# raspi.net
KiCad netlist of a schematic drawn in EAGLE
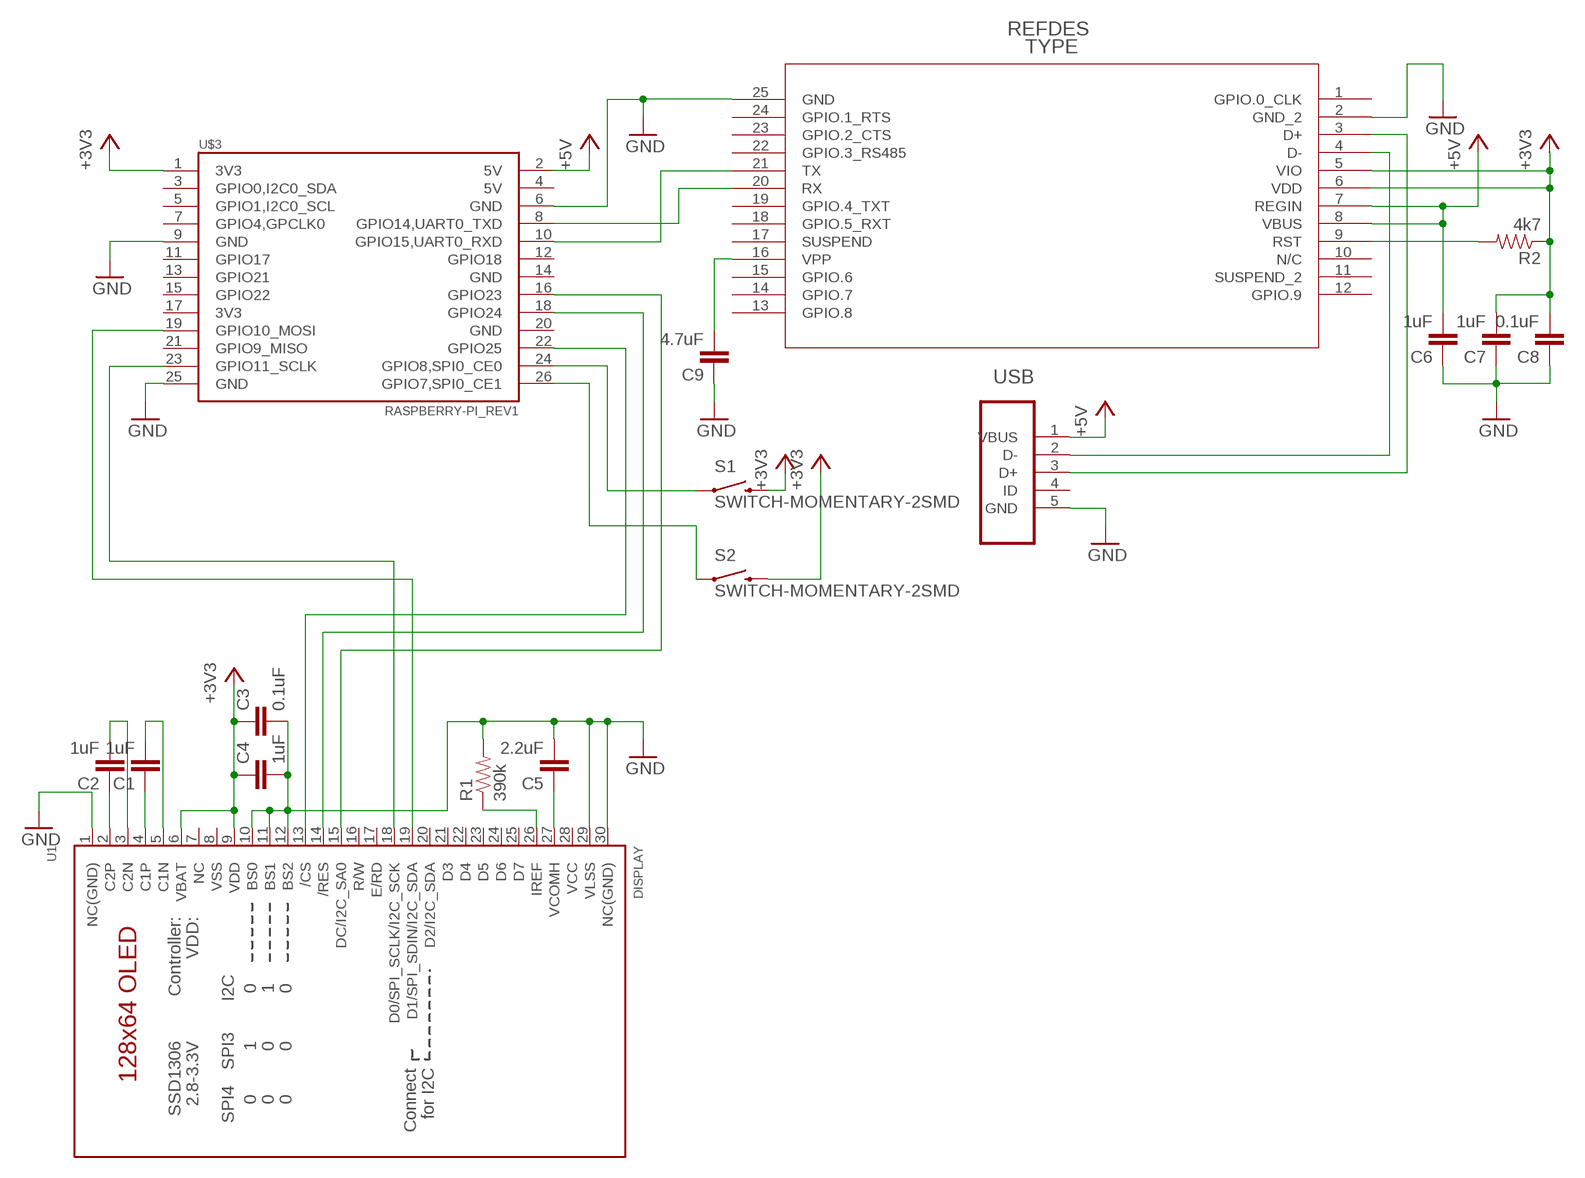
[diagram p0: schematic, sheet 1]

(export (version "E")
  (design (tool "Eeschema 10.0.6"))
  (components
    (comp (ref "C1")
      (value "1uF")
      (footprint "eagle-import:0805")
      (libsource (lib "eagle-import") (part "CAP0805"))
    )
    (comp (ref "C2")
      (value "1uF")
      (footprint "eagle-import:0805")
      (libsource (lib "eagle-import") (part "CAP0805"))
    )
    (comp (ref "C3")
      (value "0.1uF")
      (footprint "eagle-import:0805")
      (libsource (lib "eagle-import") (part "CAP0805"))
    )
    (comp (ref "C4")
      (value "1uF")
      (footprint "eagle-import:0805")
      (libsource (lib "eagle-import") (part "CAP0805"))
    )
    (comp (ref "C5")
      (value "2.2uF")
      (footprint "eagle-import:0805")
      (libsource (lib "eagle-import") (part "CAP0805"))
    )
    (comp (ref "C6")
      (value "1uF")
      (footprint "eagle-import:0805")
      (libsource (lib "eagle-import") (part "CAP0805"))
    )
    (comp (ref "C7")
      (value "1uF")
      (footprint "eagle-import:0805")
      (libsource (lib "eagle-import") (part "CAP0805"))
    )
    (comp (ref "C8")
      (value "0.1uF")
      (footprint "eagle-import:0805")
      (libsource (lib "eagle-import") (part "CAP0805"))
    )
    (comp (ref "C9")
      (value "4.7uF")
      (footprint "eagle-import:0805")
      (libsource (lib "eagle-import") (part "CAP0805"))
    )
    (comp (ref "R1")
      (value "390k")
      (footprint "eagle-import:0805")
      (libsource (lib "eagle-import") (part "RESISTOR0805-RES"))
    )
    (comp (ref "R2")
      (value "4k7")
      (footprint "eagle-import:0805")
      (libsource (lib "eagle-import") (part "RESISTOR0805-RES"))
    )
    (comp (ref "S1")
      (value "SWITCH-MOMENTARY-2SMD")
      (footprint "eagle-import:TACTILE_SWITCH_SMD")
      (libsource (lib "eagle-import") (part "SWITCH-MOMENTARY-2SMD"))
    )
    (comp (ref "S2")
      (value "SWITCH-MOMENTARY-2SMD")
      (footprint "eagle-import:TACTILE_SWITCH_SMD")
      (libsource (lib "eagle-import") (part "SWITCH-MOMENTARY-2SMD"))
    )
    (comp (ref "U$3")
      (value "RASPBERRY-PI_REV1")
      (footprint "eagle-import:RASPBERRY-PI_REV1")
      (libsource (lib "eagle-import") (part "RASPBERRY-PI_REV1"))
    )
    (comp (ref "U1")
      (value "DISPLAY")
      (footprint "eagle-import:UG-2864HSWEG01_0.96IN_WRAPAROUND")
      (libsource (lib "eagle-import") (part "DISP_OLED_UG-2864HSWEG010.96{dblquote}"))
    )
    (comp (ref "U2")
      (value "CP2110-F01-GM")
      (footprint "eagle-import:CP2110-F01-GM")
      (libsource (lib "eagle-import") (part "CP2110-F01-GM"))
    )
    (comp (ref "USB")
      (value "47346-0001")
      (footprint "eagle-import:MOLEX_47346-0001")
      (libsource (lib "eagle-import") (part "47346-0001"))
    )
  )
  (nets
    (net (code "1") (name "+3V3") (class "Default")
      (node (ref "C3") (pin "1") (pinfunction "1_1") (pintype "passive"))
      (node (ref "C4") (pin "1") (pinfunction "1_1") (pintype "passive"))
      (node (ref "C7") (pin "2") (pinfunction "2_2") (pintype "passive"))
      (node (ref "C8") (pin "2") (pinfunction "2_2") (pintype "passive"))
      (node (ref "R2") (pin "1") (pinfunction "1_1") (pintype "passive"))
      (node (ref "S1") (pin "3") (pinfunction "2_3") (pintype "passive"))
      (node (ref "S2") (pin "3") (pinfunction "2_3") (pintype "passive"))
      (node (ref "U$3") (pin "1") (pinfunction "3V3_1") (pintype "bidirectional"))
      (node (ref "U1") (pin "6") (pinfunction "VBAT_6") (pintype "input"))
      (node (ref "U1") (pin "9") (pinfunction "VDD_9") (pintype "power_in"))
      (node (ref "U2") (pin "5") (pinfunction "VIO_5") (pintype "passive"))
      (node (ref "U2") (pin "6") (pinfunction "VDD_6") (pintype "passive"))
    )
    (net (code "2") (name "+5V") (class "Default")
      (node (ref "C6") (pin "2") (pinfunction "2_2") (pintype "passive"))
      (node (ref "U$3") (pin "2") (pinfunction "5V_2") (pintype "bidirectional"))
      (node (ref "U2") (pin "7") (pinfunction "REGIN_7") (pintype "passive"))
      (node (ref "U2") (pin "8") (pinfunction "VBUS_8") (pintype "passive"))
      (node (ref "USB") (pin "1") (pinfunction "VBUS_1") (pintype "input"))
    )
    (net (code "3") (name "/VCC") (class "Default")
      (node (ref "U1") (pin "28") (pinfunction "VCC_28") (pintype "power_in"))
    )
    (net (code "4") (name "/VSS") (class "Default")
      (node (ref "U1") (pin "8") (pinfunction "VSS_8") (pintype "power_in"))
    )
    (net (code "5") (name "GND") (class "Default")
      (node (ref "C3") (pin "2") (pinfunction "2_2") (pintype "passive"))
      (node (ref "C4") (pin "2") (pinfunction "2_2") (pintype "passive"))
      (node (ref "C5") (pin "2") (pinfunction "2_2") (pintype "passive"))
      (node (ref "C6") (pin "1") (pinfunction "1_1") (pintype "passive"))
      (node (ref "C7") (pin "1") (pinfunction "1_1") (pintype "passive"))
      (node (ref "C8") (pin "1") (pinfunction "1_1") (pintype "passive"))
      (node (ref "C9") (pin "1") (pinfunction "1_1") (pintype "passive"))
      (node (ref "R1") (pin "2") (pinfunction "2_2") (pintype "passive"))
      (node (ref "U$3") (pin "25") (pinfunction "GND_25") (pintype "bidirectional"))
      (node (ref "U$3") (pin "6") (pinfunction "GND_6") (pintype "bidirectional"))
      (node (ref "U$3") (pin "9") (pinfunction "GND_9") (pintype "bidirectional"))
      (node (ref "U1") (pin "1") (pinfunction "NC(GND)_1") (pintype "input"))
      (node (ref "U1") (pin "10") (pinfunction "BS0_10") (pintype "input"))
      (node (ref "U1") (pin "11") (pinfunction "BS1_11") (pintype "input"))
      (node (ref "U1") (pin "12") (pinfunction "BS2_12") (pintype "input"))
      (node (ref "U1") (pin "29") (pinfunction "VLSS_29") (pintype "power_in"))
      (node (ref "U1") (pin "30") (pinfunction "NC(GND)_30") (pintype "input"))
      (node (ref "U2") (pin "2") (pinfunction "GND_2_2") (pintype "passive"))
      (node (ref "U2") (pin "25") (pinfunction "GND_25") (pintype "passive"))
      (node (ref "USB") (pin "5") (pinfunction "GND_5") (pintype "input"))
    )
    (net (code "6") (name "Net-(U$3-GPIO7,SPI0_CE1)") (class "Default")
      (node (ref "S2") (pin "1") (pinfunction "1_1") (pintype "passive"))
      (node (ref "U$3") (pin "26") (pinfunction "GPIO7,SPI0_CE1_26") (pintype "bidirectional"))
    )
    (net (code "7") (name "Net-(U$3-GPIO8,SPI0_CE0)") (class "Default")
      (node (ref "S1") (pin "1") (pinfunction "1_1") (pintype "passive"))
      (node (ref "U$3") (pin "24") (pinfunction "GPIO8,SPI0_CE0_24") (pintype "bidirectional"))
    )
    (net (code "8") (name "Net-(U$3-GPIO10_MOSI)") (class "Default")
      (node (ref "U$3") (pin "19") (pinfunction "GPIO10_MOSI_19") (pintype "bidirectional"))
      (node (ref "U1") (pin "19") (pinfunction "D1/SPI_SDIN/I2C_SDA_19") (pintype "bidirectional"))
    )
    (net (code "9") (name "Net-(U$3-GPIO11_SCLK)") (class "Default")
      (node (ref "U$3") (pin "23") (pinfunction "GPIO11_SCLK_23") (pintype "bidirectional"))
      (node (ref "U1") (pin "18") (pinfunction "D0/SPI_SCLK/I2C_SCK_18") (pintype "bidirectional"))
    )
    (net (code "10") (name "Net-(U$3-GPIO14,UART0_TXD)") (class "Default")
      (node (ref "U$3") (pin "8") (pinfunction "GPIO14,UART0_TXD_8") (pintype "bidirectional"))
      (node (ref "U2") (pin "20") (pinfunction "RX_20") (pintype "passive"))
    )
    (net (code "11") (name "Net-(U$3-GPIO15,UART0_RXD)") (class "Default")
      (node (ref "U$3") (pin "10") (pinfunction "GPIO15,UART0_RXD_10") (pintype "bidirectional"))
      (node (ref "U2") (pin "21") (pinfunction "TX_21") (pintype "passive"))
    )
    (net (code "12") (name "Net-(U$3-GPIO23)") (class "Default")
      (node (ref "U$3") (pin "16") (pinfunction "GPIO23_16") (pintype "bidirectional"))
      (node (ref "U1") (pin "15") (pinfunction "DC/I2C_SA0_15") (pintype "input"))
    )
    (net (code "13") (name "Net-(U$3-GPIO24)") (class "Default")
      (node (ref "U$3") (pin "18") (pinfunction "GPIO24_18") (pintype "bidirectional"))
      (node (ref "U1") (pin "14") (pinfunction "/RES_14") (pintype "input"))
    )
    (net (code "14") (name "Net-(U$3-GPIO25)") (class "Default")
      (node (ref "U$3") (pin "22") (pinfunction "GPIO25_22") (pintype "bidirectional"))
      (node (ref "U1") (pin "13") (pinfunction "/CS_13") (pintype "input"))
    )
    (net (code "15") (name "Net-(U1-C1N)") (class "Default")
      (node (ref "C1") (pin "2") (pinfunction "2_2") (pintype "passive"))
      (node (ref "U1") (pin "5") (pinfunction "C1N_5") (pintype "input"))
    )
    (net (code "16") (name "Net-(U1-C1P)") (class "Default")
      (node (ref "C1") (pin "1") (pinfunction "1_1") (pintype "passive"))
      (node (ref "U1") (pin "4") (pinfunction "C1P_4") (pintype "input"))
    )
    (net (code "17") (name "Net-(U1-C2N)") (class "Default")
      (node (ref "C2") (pin "2") (pinfunction "2_2") (pintype "passive"))
      (node (ref "U1") (pin "3") (pinfunction "C2N_3") (pintype "input"))
    )
    (net (code "18") (name "Net-(U1-C2P)") (class "Default")
      (node (ref "C2") (pin "1") (pinfunction "1_1") (pintype "passive"))
      (node (ref "U1") (pin "2") (pinfunction "C2P_2") (pintype "input"))
    )
    (net (code "19") (name "Net-(U1-IREF)") (class "Default")
      (node (ref "R1") (pin "1") (pinfunction "1_1") (pintype "passive"))
      (node (ref "U1") (pin "26") (pinfunction "IREF_26") (pintype "input"))
    )
    (net (code "20") (name "Net-(U1-VCOMH)") (class "Default")
      (node (ref "C5") (pin "1") (pinfunction "1_1") (pintype "passive"))
      (node (ref "U1") (pin "27") (pinfunction "VCOMH_27") (pintype "output"))
    )
    (net (code "21") (name "Net-(U2-D+)") (class "Default")
      (node (ref "U2") (pin "3") (pinfunction "D+_3") (pintype "passive"))
      (node (ref "USB") (pin "3") (pinfunction "D+_3") (pintype "input"))
    )
    (net (code "22") (name "Net-(U2-D-)") (class "Default")
      (node (ref "U2") (pin "4") (pinfunction "D-_4") (pintype "passive"))
      (node (ref "USB") (pin "2") (pinfunction "D-_2") (pintype "input"))
    )
    (net (code "23") (name "Net-(U2-RST)") (class "Default")
      (node (ref "R2") (pin "2") (pinfunction "2_2") (pintype "passive"))
      (node (ref "U2") (pin "9") (pinfunction "RST_9") (pintype "passive"))
    )
    (net (code "24") (name "Net-(U2-VPP)") (class "Default")
      (node (ref "C9") (pin "2") (pinfunction "2_2") (pintype "passive"))
      (node (ref "U2") (pin "16") (pinfunction "VPP_16") (pintype "passive"))
    )
    (net (code "25") (name "unconnected-(U$3-3V3-Pad17)") (class "Default")
      (node (ref "U$3") (pin "17") (pinfunction "3V3_17") (pintype "bidirectional"))
    )
    (net (code "26") (name "unconnected-(U$3-5V-Pad4)") (class "Default")
      (node (ref "U$3") (pin "4") (pinfunction "5V_4") (pintype "bidirectional"))
    )
    (net (code "27") (name "unconnected-(U$3-GND-Pad14)") (class "Default")
      (node (ref "U$3") (pin "14") (pinfunction "GND_14") (pintype "bidirectional"))
    )
    (net (code "28") (name "unconnected-(U$3-GND-Pad20)") (class "Default")
      (node (ref "U$3") (pin "20") (pinfunction "GND_20") (pintype "bidirectional"))
    )
    (net (code "29") (name "unconnected-(U$3-GPIO0,I2C0_SDA-Pad3)") (class "Default")
      (node (ref "U$3") (pin "3") (pinfunction "GPIO0,I2C0_SDA_3") (pintype "bidirectional"))
    )
    (net (code "30") (name "unconnected-(U$3-GPIO1,I2C0_SCL-Pad5)") (class "Default")
      (node (ref "U$3") (pin "5") (pinfunction "GPIO1,I2C0_SCL_5") (pintype "bidirectional"))
    )
    (net (code "31") (name "unconnected-(U$3-GPIO4,GPCLK0-Pad7)") (class "Default")
      (node (ref "U$3") (pin "7") (pinfunction "GPIO4,GPCLK0_7") (pintype "bidirectional"))
    )
    (net (code "32") (name "unconnected-(U$3-GPIO9_MISO-Pad21)") (class "Default")
      (node (ref "U$3") (pin "21") (pinfunction "GPIO9_MISO_21") (pintype "bidirectional"))
    )
    (net (code "33") (name "unconnected-(U$3-GPIO17-Pad11)") (class "Default")
      (node (ref "U$3") (pin "11") (pinfunction "GPIO17_11") (pintype "bidirectional"))
    )
    (net (code "34") (name "unconnected-(U$3-GPIO18-Pad12)") (class "Default")
      (node (ref "U$3") (pin "12") (pinfunction "GPIO18_12") (pintype "bidirectional"))
    )
    (net (code "35") (name "unconnected-(U$3-GPIO21-Pad13)") (class "Default")
      (node (ref "U$3") (pin "13") (pinfunction "GPIO21_13") (pintype "bidirectional"))
    )
    (net (code "36") (name "unconnected-(U$3-GPIO22-Pad15)") (class "Default")
      (node (ref "U$3") (pin "15") (pinfunction "GPIO22_15") (pintype "bidirectional"))
    )
    (net (code "37") (name "unconnected-(U1-D2{slash}I2C_SDA-Pad20)") (class "Default")
      (node (ref "U1") (pin "20") (pinfunction "D2/I2C_SDA_20") (pintype "bidirectional"))
    )
    (net (code "38") (name "unconnected-(U1-D3-Pad21)") (class "Default")
      (node (ref "U1") (pin "21") (pinfunction "D3_21") (pintype "bidirectional"))
    )
    (net (code "39") (name "unconnected-(U1-D4-Pad22)") (class "Default")
      (node (ref "U1") (pin "22") (pinfunction "D4_22") (pintype "bidirectional"))
    )
    (net (code "40") (name "unconnected-(U1-D5-Pad23)") (class "Default")
      (node (ref "U1") (pin "23") (pinfunction "D5_23") (pintype "bidirectional"))
    )
    (net (code "41") (name "unconnected-(U1-D6-Pad24)") (class "Default")
      (node (ref "U1") (pin "24") (pinfunction "D6_24") (pintype "bidirectional"))
    )
    (net (code "42") (name "unconnected-(U1-D7-Pad25)") (class "Default")
      (node (ref "U1") (pin "25") (pinfunction "D7_25") (pintype "bidirectional"))
    )
    (net (code "43") (name "unconnected-(U1-E{slash}RD-Pad17)") (class "Default")
      (node (ref "U1") (pin "17") (pinfunction "E/RD_17") (pintype "input"))
    )
    (net (code "44") (name "unconnected-(U1-NC-Pad7)") (class "Default")
      (node (ref "U1") (pin "7") (pinfunction "NC_7") (pintype "no_connect"))
    )
    (net (code "45") (name "unconnected-(U1-R{slash}W-Pad16)") (class "Default")
      (node (ref "U1") (pin "16") (pinfunction "R/W_16") (pintype "input"))
    )
    (net (code "46") (name "unconnected-(U2-GPIO.0_CLK-Pad1)") (class "Default")
      (node (ref "U2") (pin "1") (pinfunction "GPIO.0_CLK_1") (pintype "passive"))
    )
    (net (code "47") (name "unconnected-(U2-GPIO.1_RTS-Pad24)") (class "Default")
      (node (ref "U2") (pin "24") (pinfunction "GPIO.1_RTS_24") (pintype "passive"))
    )
    (net (code "48") (name "unconnected-(U2-GPIO.2_CTS-Pad23)") (class "Default")
      (node (ref "U2") (pin "23") (pinfunction "GPIO.2_CTS_23") (pintype "passive"))
    )
    (net (code "49") (name "unconnected-(U2-GPIO.3_RS485-Pad22)") (class "Default")
      (node (ref "U2") (pin "22") (pinfunction "GPIO.3_RS485_22") (pintype "passive"))
    )
    (net (code "50") (name "unconnected-(U2-GPIO.4_TXT-Pad19)") (class "Default")
      (node (ref "U2") (pin "19") (pinfunction "GPIO.4_TXT_19") (pintype "passive"))
    )
    (net (code "51") (name "unconnected-(U2-GPIO.5_RXT-Pad18)") (class "Default")
      (node (ref "U2") (pin "18") (pinfunction "GPIO.5_RXT_18") (pintype "passive"))
    )
    (net (code "52") (name "unconnected-(U2-GPIO.6-Pad15)") (class "Default")
      (node (ref "U2") (pin "15") (pinfunction "GPIO.6_15") (pintype "passive"))
    )
    (net (code "53") (name "unconnected-(U2-GPIO.7-Pad14)") (class "Default")
      (node (ref "U2") (pin "14") (pinfunction "GPIO.7_14") (pintype "passive"))
    )
    (net (code "54") (name "unconnected-(U2-GPIO.8-Pad13)") (class "Default")
      (node (ref "U2") (pin "13") (pinfunction "GPIO.8_13") (pintype "passive"))
    )
    (net (code "55") (name "unconnected-(U2-GPIO.9-Pad12)") (class "Default")
      (node (ref "U2") (pin "12") (pinfunction "GPIO.9_12") (pintype "passive"))
    )
    (net (code "56") (name "unconnected-(U2-N{slash}C-Pad10)") (class "Default")
      (node (ref "U2") (pin "10") (pinfunction "N/C_10") (pintype "passive"))
    )
    (net (code "57") (name "unconnected-(U2-SUSPEND-Pad17)") (class "Default")
      (node (ref "U2") (pin "17") (pinfunction "SUSPEND_17") (pintype "passive"))
    )
    (net (code "58") (name "unconnected-(U2-SUSPEND_2-Pad11)") (class "Default")
      (node (ref "U2") (pin "11") (pinfunction "SUSPEND_2_11") (pintype "passive"))
    )
    (net (code "59") (name "unconnected-(USB-ID-Pad4)") (class "Default")
      (node (ref "USB") (pin "4") (pinfunction "ID_4") (pintype "input"))
    )
  )
)
